# New_Project.net
KiCad netlist of a schematic drawn in EasyEDA
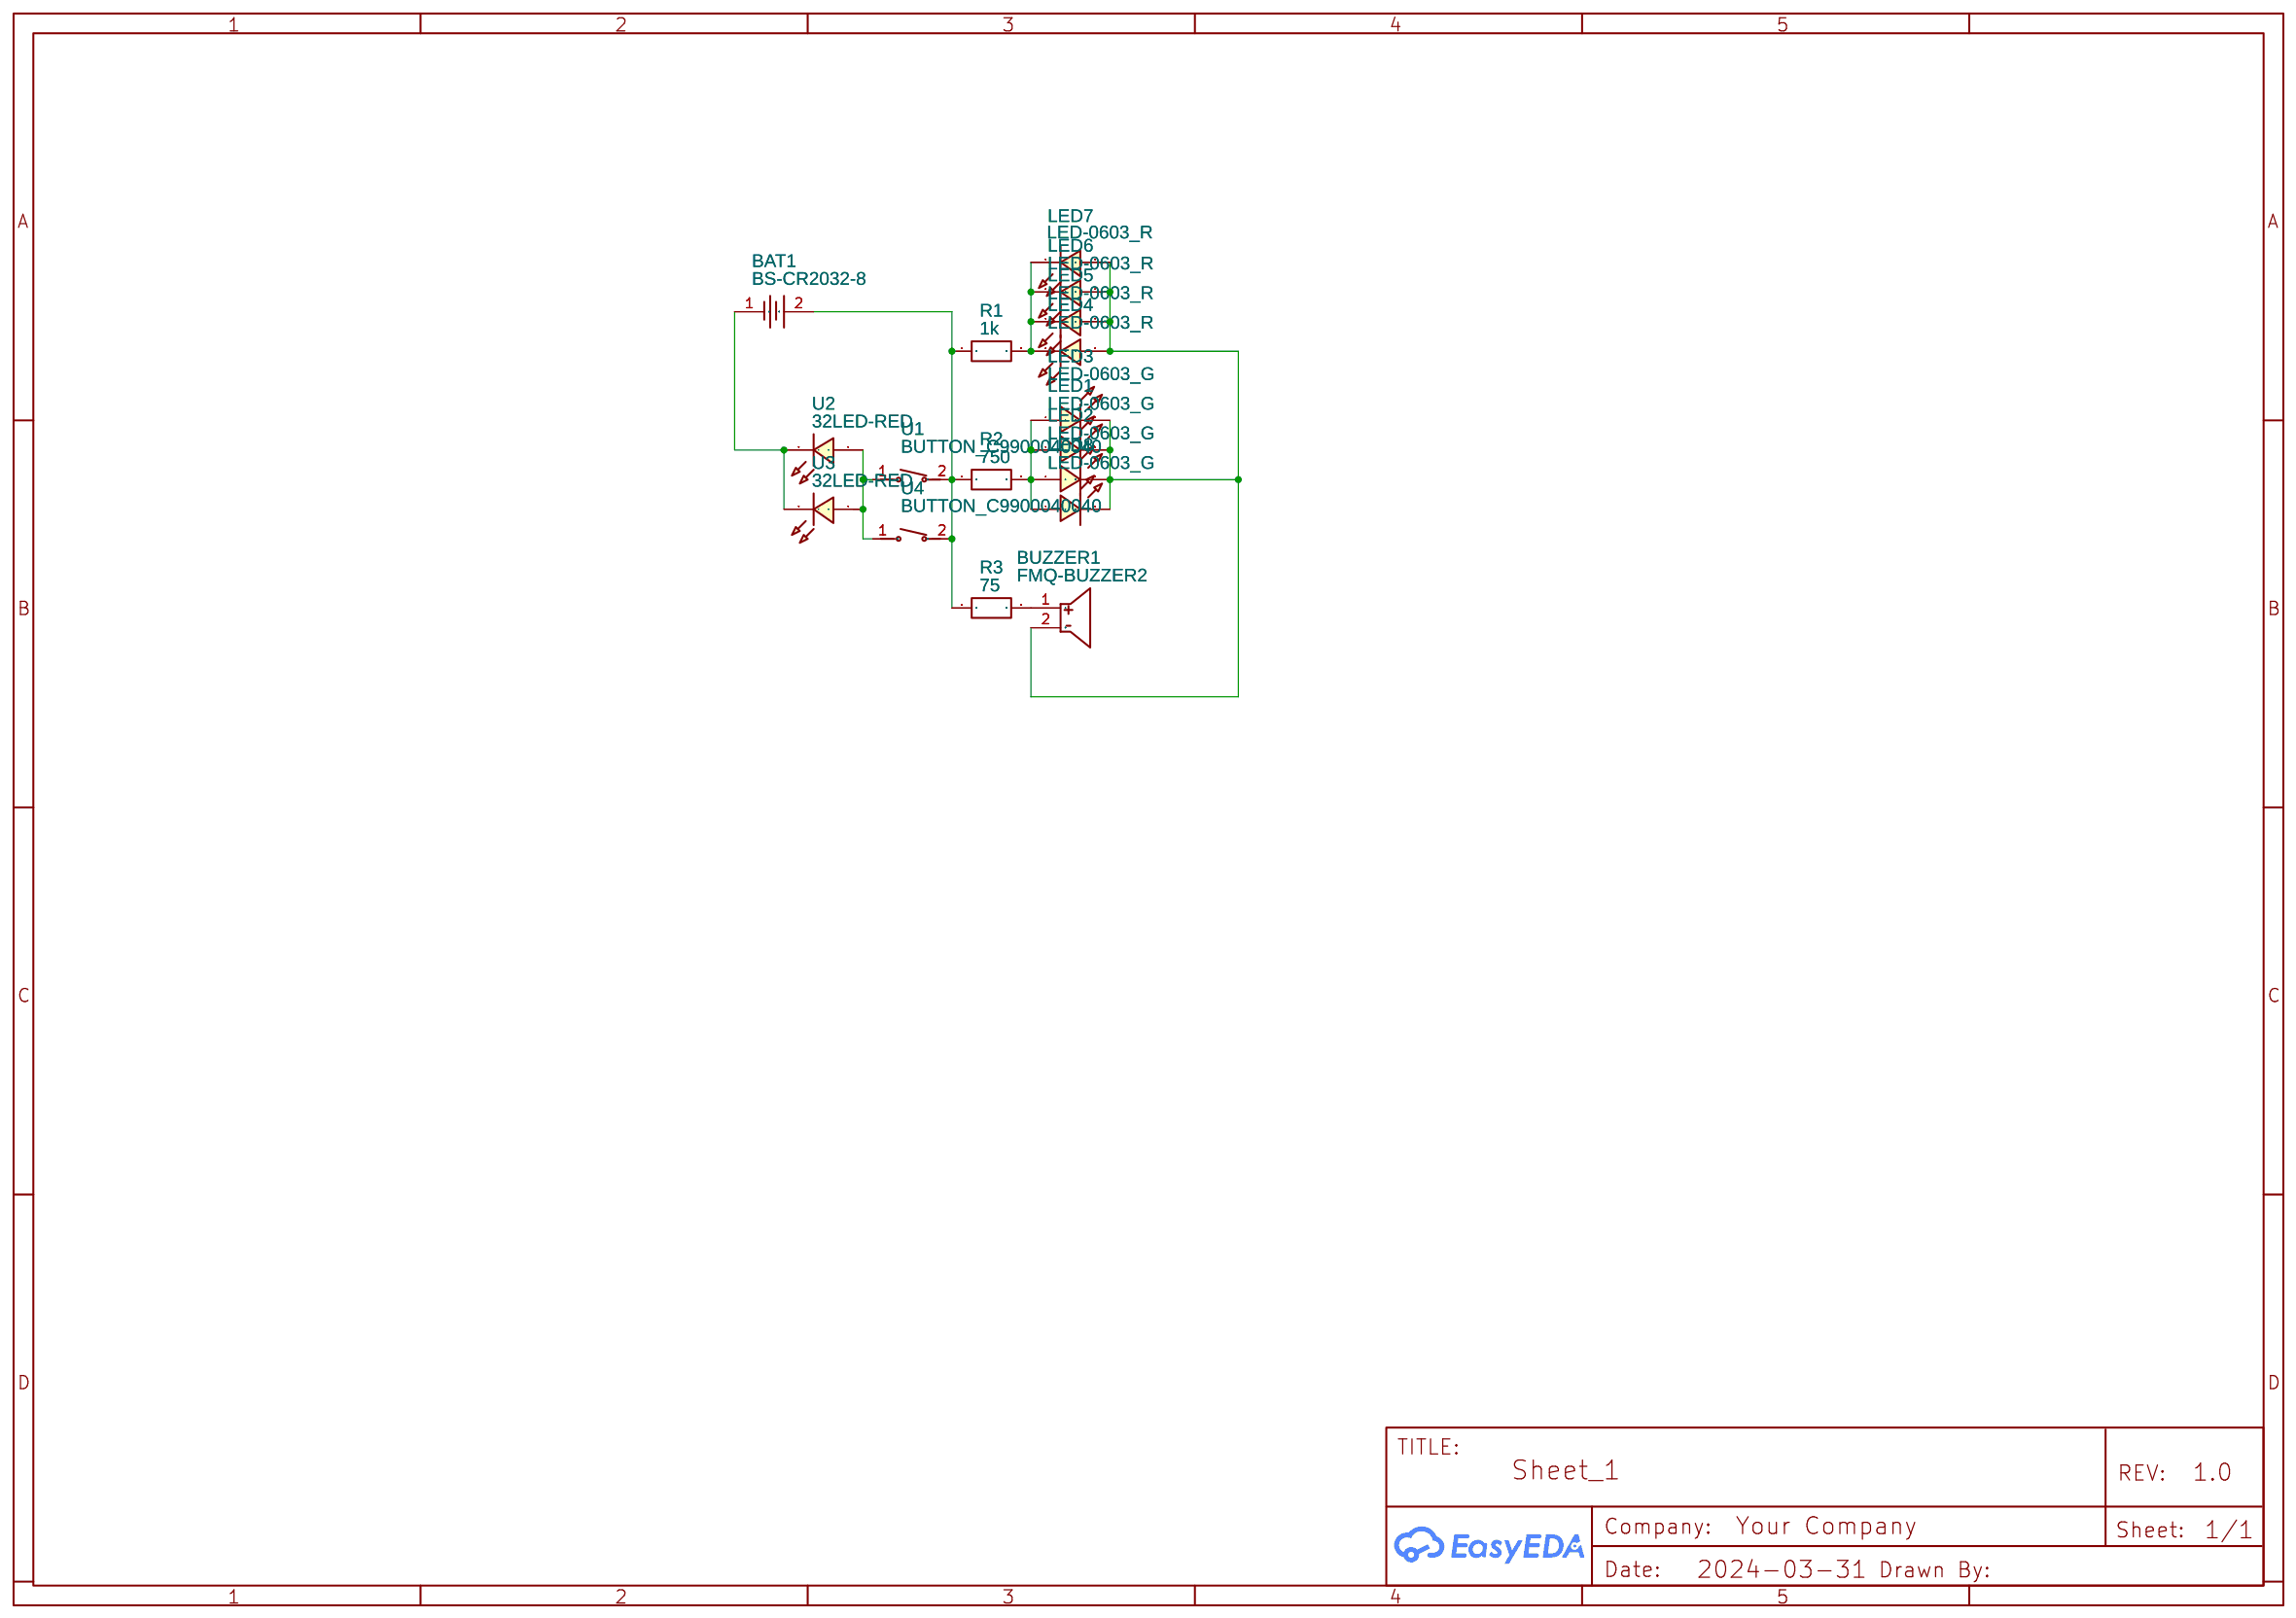
[diagram p0: schematic sheet]

(export (version "E")
  (design (tool "Eeschema 10.0.6"))
  (components
    (comp (ref "BAT1")
      (value "BS-CR2032-8")
      (fields (field (name "Manufacturer") "LX(连欣科技)"))
      (libsource (lib "") (part "BS-CR2032-8"))
    )
    (comp (ref "BUZZER1") (value "FMQ-BUZZER2") (libsource (lib "") (part "FMQ-BUZZER2")))
    (comp (ref "LED1")
      (value "LED-0603_G")
      (fields
        (field (name "Manufacturer Part") "19-217/GHC-YR1S2/3T")
        (field (name "Manufacturer") "EVERLIGHT(台湾亿光)")
      )
      (libsource (lib "") (part "LED-0603_G"))
    )
    (comp (ref "LED2")
      (value "LED-0603_G")
      (fields
        (field (name "Manufacturer Part") "19-217/GHC-YR1S2/3T")
        (field (name "Manufacturer") "EVERLIGHT(台湾亿光)")
      )
      (libsource (lib "") (part "LED-0603_G"))
    )
    (comp (ref "LED3")
      (value "LED-0603_G")
      (fields
        (field (name "Manufacturer Part") "19-217/GHC-YR1S2/3T")
        (field (name "Manufacturer") "EVERLIGHT(台湾亿光)")
      )
      (libsource (lib "") (part "LED-0603_G"))
    )
    (comp (ref "LED4")
      (value "LED-0603_R")
      (fields
        (field (name "Manufacturer Part") "19-217/R6C-AL1M2VY/3T")
        (field (name "Manufacturer") "EVERLIGHT(台湾亿光)")
      )
      (libsource (lib "") (part "LED-0603_R"))
    )
    (comp (ref "LED5")
      (value "LED-0603_R")
      (fields
        (field (name "Manufacturer Part") "19-217/R6C-AL1M2VY/3T")
        (field (name "Manufacturer") "EVERLIGHT(台湾亿光)")
      )
      (libsource (lib "") (part "LED-0603_R"))
    )
    (comp (ref "LED6")
      (value "LED-0603_R")
      (fields
        (field (name "Manufacturer Part") "19-217/R6C-AL1M2VY/3T")
        (field (name "Manufacturer") "EVERLIGHT(台湾亿光)")
      )
      (libsource (lib "") (part "LED-0603_R"))
    )
    (comp (ref "LED7")
      (value "LED-0603_R")
      (fields
        (field (name "Manufacturer Part") "19-217/R6C-AL1M2VY/3T")
        (field (name "Manufacturer") "EVERLIGHT(台湾亿光)")
      )
      (libsource (lib "") (part "LED-0603_R"))
    )
    (comp (ref "LED8")
      (value "LED-0603_G")
      (fields
        (field (name "Manufacturer Part") "19-217/GHC-YR1S2/3T")
        (field (name "Manufacturer") "EVERLIGHT(台湾亿光)")
      )
      (libsource (lib "") (part "LED-0603_G"))
    )
    (comp (ref "R1") (value "1k") (libsource (lib "") (part "R_1206_EU")))
    (comp (ref "R2") (value "750") (libsource (lib "") (part "R_1206_EU")))
    (comp (ref "R3") (value "75") (libsource (lib "") (part "R_1206_EU")))
    (comp (ref "U1")
      (value "BUTTON_C9900040040")
      (fields (field (name "Manufacturer Part") "BUTTON"))
      (libsource (lib "") (part "BUTTON_C9900040040"))
    )
    (comp (ref "U2")
      (value "32LED-RED")
      (fields (field (name "Manufacturer") "Grayhill"))
      (libsource (lib "") (part "32LED-RED"))
    )
    (comp (ref "U3")
      (value "32LED-RED")
      (fields (field (name "Manufacturer") "Grayhill"))
      (libsource (lib "") (part "32LED-RED"))
    )
    (comp (ref "U4")
      (value "BUTTON_C9900040040")
      (fields (field (name "Manufacturer Part") "BUTTON"))
      (libsource (lib "") (part "BUTTON_C9900040040"))
    )
  )
  (nets
    (net (code "1") (name "Net-(BUZZER1-Pad1)") (class "Default")
      (node (ref "BUZZER1") (pin "1") (pinfunction "1_1") (pintype "unspecified"))
      (node (ref "R3") (pin "2") (pinfunction "2_2") (pintype "unspecified"))
    )
    (net (code "2") (name "Net-(BUZZER1-Pad2)") (class "Default")
      (node (ref "BUZZER1") (pin "2") (pinfunction "2_2") (pintype "unspecified"))
      (node (ref "LED1") (pin "2") (pinfunction "2_2") (pintype "unspecified"))
      (node (ref "LED2") (pin "2") (pinfunction "2_2") (pintype "unspecified"))
      (node (ref "LED3") (pin "2") (pinfunction "2_2") (pintype "unspecified"))
      (node (ref "LED4") (pin "1") (pinfunction "1_1") (pintype "unspecified"))
      (node (ref "LED5") (pin "1") (pinfunction "1_1") (pintype "unspecified"))
      (node (ref "LED6") (pin "1") (pinfunction "1_1") (pintype "unspecified"))
      (node (ref "LED7") (pin "1") (pinfunction "1_1") (pintype "unspecified"))
      (node (ref "LED8") (pin "2") (pinfunction "2_2") (pintype "unspecified"))
    )
    (net (code "3") (name "Net-(LED1-Pad1)") (class "Default")
      (node (ref "LED1") (pin "1") (pinfunction "1_1") (pintype "unspecified"))
      (node (ref "LED2") (pin "1") (pinfunction "1_1") (pintype "unspecified"))
      (node (ref "LED3") (pin "1") (pinfunction "1_1") (pintype "unspecified"))
      (node (ref "LED8") (pin "1") (pinfunction "1_1") (pintype "unspecified"))
      (node (ref "R2") (pin "2") (pinfunction "2_2") (pintype "unspecified"))
    )
    (net (code "4") (name "Net-(LED4-Pad2)") (class "Default")
      (node (ref "LED4") (pin "2") (pinfunction "2_2") (pintype "unspecified"))
      (node (ref "LED5") (pin "2") (pinfunction "2_2") (pintype "unspecified"))
      (node (ref "LED6") (pin "2") (pinfunction "2_2") (pintype "unspecified"))
      (node (ref "LED7") (pin "2") (pinfunction "2_2") (pintype "unspecified"))
      (node (ref "R1") (pin "2") (pinfunction "2_2") (pintype "unspecified"))
    )
    (net (code "5") (name "Net-(U1-A)") (class "Default")
      (node (ref "U1") (pin "1") (pinfunction "A_1") (pintype "unspecified"))
      (node (ref "U2") (pin "1") (pinfunction "+_1") (pintype "unspecified"))
      (node (ref "U3") (pin "1") (pinfunction "+_1") (pintype "unspecified"))
      (node (ref "U4") (pin "1") (pinfunction "A_1") (pintype "unspecified"))
    )
    (net (code "6") (name "Net-(U1-B)") (class "Default")
      (node (ref "BAT1") (pin "2") (pinfunction "2_2") (pintype "input"))
      (node (ref "R1") (pin "1") (pinfunction "1_1") (pintype "unspecified"))
      (node (ref "R2") (pin "1") (pinfunction "1_1") (pintype "unspecified"))
      (node (ref "R3") (pin "1") (pinfunction "1_1") (pintype "unspecified"))
      (node (ref "U1") (pin "2") (pinfunction "B_2") (pintype "unspecified"))
      (node (ref "U4") (pin "2") (pinfunction "B_2") (pintype "unspecified"))
    )
    (net (code "7") (name "Net-(U2--)") (class "Default")
      (node (ref "BAT1") (pin "1") (pinfunction "1_1") (pintype "input"))
      (node (ref "U2") (pin "2") (pinfunction "-_2") (pintype "unspecified"))
      (node (ref "U3") (pin "2") (pinfunction "-_2") (pintype "unspecified"))
    )
  )
)
